# USB.net
KiCad netlist of a schematic drawn in Altium Designer
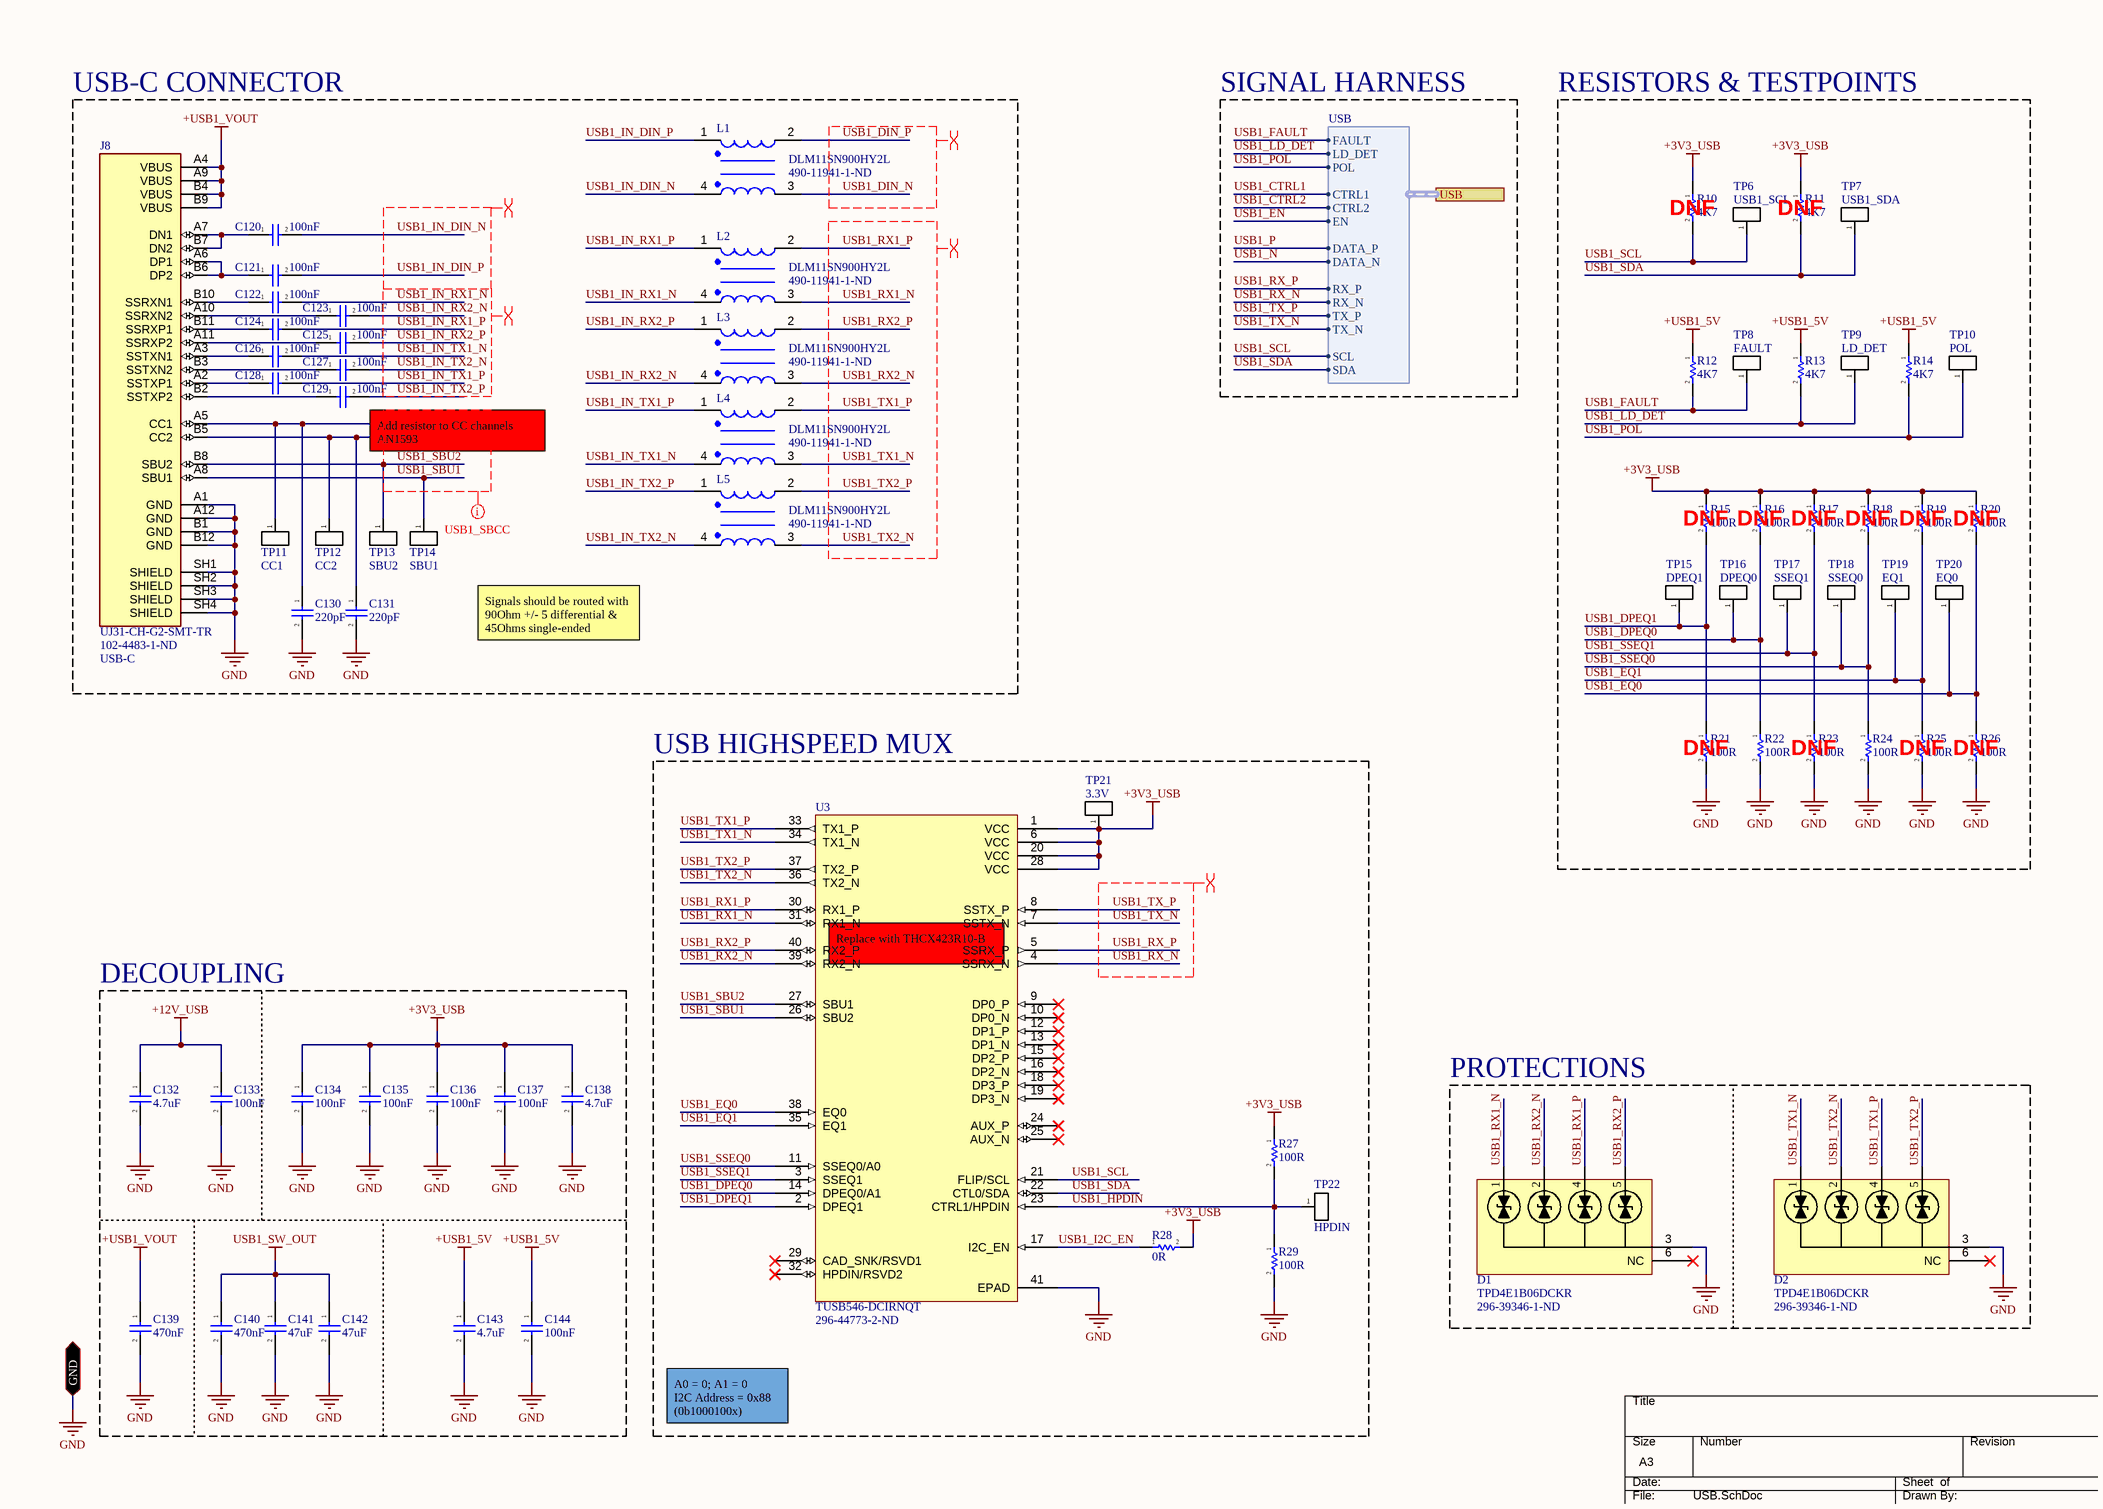
[diagram p0: USB.SchDoc]

(export (version "E")
  (design (tool "Eeschema 10.0.6"))
  (components
    (comp (ref "C120")
      (value "100nF")
      (footprint "CAP_0402")
      (description "Generic SMT Ceramic Capacitor")
      (libsource (lib "Symbols") (part "CAP_CER"))
    )
    (comp (ref "C121")
      (value "100nF")
      (footprint "CAP_0402")
      (description "Generic SMT Ceramic Capacitor")
      (libsource (lib "Symbols") (part "CAP_CER"))
    )
    (comp (ref "C122")
      (value "100nF")
      (footprint "CAP_0402")
      (description "Generic SMT Ceramic Capacitor")
      (libsource (lib "Symbols") (part "CAP_CER"))
    )
    (comp (ref "C123")
      (value "100nF")
      (footprint "CAP_0402")
      (description "Generic SMT Ceramic Capacitor")
      (libsource (lib "Symbols") (part "CAP_CER"))
    )
    (comp (ref "C124")
      (value "100nF")
      (footprint "CAP_0402")
      (description "Generic SMT Ceramic Capacitor")
      (libsource (lib "Symbols") (part "CAP_CER"))
    )
    (comp (ref "C125")
      (value "100nF")
      (footprint "CAP_0402")
      (description "Generic SMT Ceramic Capacitor")
      (libsource (lib "Symbols") (part "CAP_CER"))
    )
    (comp (ref "C126")
      (value "100nF")
      (footprint "CAP_0402")
      (description "Generic SMT Ceramic Capacitor")
      (libsource (lib "Symbols") (part "CAP_CER"))
    )
    (comp (ref "C127")
      (value "100nF")
      (footprint "CAP_0402")
      (description "Generic SMT Ceramic Capacitor")
      (libsource (lib "Symbols") (part "CAP_CER"))
    )
    (comp (ref "C128")
      (value "100nF")
      (footprint "CAP_0402")
      (description "Generic SMT Ceramic Capacitor")
      (libsource (lib "Symbols") (part "CAP_CER"))
    )
    (comp (ref "C129")
      (value "100nF")
      (footprint "CAP_0402")
      (description "Generic SMT Ceramic Capacitor")
      (libsource (lib "Symbols") (part "CAP_CER"))
    )
    (comp (ref "C130")
      (value "220pF")
      (footprint "CAP_0402")
      (description "Generic SMT Ceramic Capacitor")
      (libsource (lib "Symbols") (part "CAP_CER"))
    )
    (comp (ref "C131")
      (value "220pF")
      (footprint "CAP_0402")
      (description "Generic SMT Ceramic Capacitor")
      (libsource (lib "Symbols") (part "CAP_CER"))
    )
    (comp (ref "C132")
      (value "4.7uF")
      (footprint "CAP_0805")
      (description "Generic SMT Ceramic Capacitor")
      (libsource (lib "Symbols") (part "CAP_CER"))
    )
    (comp (ref "C133")
      (value "100nF")
      (footprint "CAP_0402")
      (description "Generic SMT Ceramic Capacitor")
      (libsource (lib "Symbols") (part "CAP_CER"))
    )
    (comp (ref "C134")
      (value "100nF")
      (footprint "CAP_0402")
      (description "Generic SMT Ceramic Capacitor")
      (libsource (lib "Symbols") (part "CAP_CER"))
    )
    (comp (ref "C135")
      (value "100nF")
      (footprint "CAP_0402")
      (description "Generic SMT Ceramic Capacitor")
      (libsource (lib "Symbols") (part "CAP_CER"))
    )
    (comp (ref "C136")
      (value "100nF")
      (footprint "CAP_0402")
      (description "Generic SMT Ceramic Capacitor")
      (libsource (lib "Symbols") (part "CAP_CER"))
    )
    (comp (ref "C137")
      (value "100nF")
      (footprint "CAP_0402")
      (description "Generic SMT Ceramic Capacitor")
      (libsource (lib "Symbols") (part "CAP_CER"))
    )
    (comp (ref "C138")
      (value "4.7uF")
      (footprint "CAP_0805")
      (description "Generic SMT Ceramic Capacitor")
      (libsource (lib "Symbols") (part "CAP_CER"))
    )
    (comp (ref "C139")
      (value "470nF")
      (footprint "CAP_0402")
      (description "Generic SMT Ceramic Capacitor")
      (libsource (lib "Symbols") (part "CAP_CER"))
    )
    (comp (ref "C140")
      (value "470nF")
      (footprint "CAP_0402")
      (description "Generic SMT Ceramic Capacitor")
      (libsource (lib "Symbols") (part "CAP_CER"))
    )
    (comp (ref "C141")
      (value "47uF")
      (footprint "CAP_1206")
      (description "Generic SMT Ceramic Capacitor")
      (libsource (lib "Symbols") (part "CAP_CER"))
    )
    (comp (ref "C142")
      (value "47uF")
      (footprint "CAP_1206")
      (description "Generic SMT Ceramic Capacitor")
      (libsource (lib "Symbols") (part "CAP_CER"))
    )
    (comp (ref "C143")
      (value "4.7uF")
      (footprint "CAP_0805")
      (description "Generic SMT Ceramic Capacitor")
      (libsource (lib "Symbols") (part "CAP_CER"))
    )
    (comp (ref "C144")
      (value "100nF")
      (footprint "CAP_0402")
      (description "Generic SMT Ceramic Capacitor")
      (libsource (lib "Symbols") (part "CAP_CER"))
    )
    (comp (ref "D1")
      (value "TPD4E1B06DCKR")
      (footprint "TPD4E1B06DCKR")
      (description "TVS DIODE 5.5VWM 14.5VC SC70-6")
      (fields
        (field (name "MFR") "Texas Instruments")
        (field (name "SUPPLIER PART NUMBER 1") "296-39346-1-ND")
      )
      (libsource (lib "CryptLib") (part "DIODE_TPD4E1B06DCKR"))
    )
    (comp (ref "D2")
      (value "TPD4E1B06DCKR")
      (footprint "TPD4E1B06DCKR")
      (description "TVS DIODE 5.5VWM 14.5VC SC70-6")
      (fields
        (field (name "MFR") "Texas Instruments")
        (field (name "SUPPLIER PART NUMBER 1") "296-39346-1-ND")
      )
      (libsource (lib "CryptLib") (part "DIODE_TPD4E1B06DCKR"))
    )
    (comp (ref "J8")
      (value "UJ31-CH-G2-SMT-TR")
      (footprint "UJ31-CH-G2-SMT-TR")
      (description "Type C, USB 3.1 Gen 2, 5 A, Right Angle, Surface Mount _SMT_, USB Receptacle")
      (fields
        (field (name "MFR") "CUI Devices")
        (field (name "DIGIKEY PART NUMBER") "102-4483-1-ND")
        (field (name "CONNECTOR TYPE") "USB-C")
        (field (name "SUPPLIER PART NUMBER 1") "102-4483-1-ND")
      )
      (libsource (lib "CryptLib") (part "CONN_UJ31-CH-G2-SMT-TR"))
    )
    (comp (ref "L1")
      (value "DLM11SN900HY2L")
      (footprint "DLM11SN900HY2L")
      (description "2 Line Common Mode Choke Surface Mount 90 Ohms @ 100MHz 100mA DCR 1.38Ohm")
      (fields (field (name "SUPPLIER PART NUMBER 1") "490-11941-1-ND"))
      (libsource (lib "CryptLib") (part "IND_DLM11SN900HY2L"))
    )
    (comp (ref "L2")
      (value "DLM11SN900HY2L")
      (footprint "DLM11SN900HY2L")
      (description "2 Line Common Mode Choke Surface Mount 90 Ohms @ 100MHz 100mA DCR 1.38Ohm")
      (fields (field (name "SUPPLIER PART NUMBER 1") "490-11941-1-ND"))
      (libsource (lib "CryptLib") (part "IND_DLM11SN900HY2L"))
    )
    (comp (ref "L3")
      (value "DLM11SN900HY2L")
      (footprint "DLM11SN900HY2L")
      (description "2 Line Common Mode Choke Surface Mount 90 Ohms @ 100MHz 100mA DCR 1.38Ohm")
      (fields (field (name "SUPPLIER PART NUMBER 1") "490-11941-1-ND"))
      (libsource (lib "CryptLib") (part "IND_DLM11SN900HY2L"))
    )
    (comp (ref "L4")
      (value "DLM11SN900HY2L")
      (footprint "DLM11SN900HY2L")
      (description "2 Line Common Mode Choke Surface Mount 90 Ohms @ 100MHz 100mA DCR 1.38Ohm")
      (fields (field (name "SUPPLIER PART NUMBER 1") "490-11941-1-ND"))
      (libsource (lib "CryptLib") (part "IND_DLM11SN900HY2L"))
    )
    (comp (ref "L5")
      (value "DLM11SN900HY2L")
      (footprint "DLM11SN900HY2L")
      (description "2 Line Common Mode Choke Surface Mount 90 Ohms @ 100MHz 100mA DCR 1.38Ohm")
      (fields (field (name "SUPPLIER PART NUMBER 1") "490-11941-1-ND"))
      (libsource (lib "CryptLib") (part "IND_DLM11SN900HY2L"))
    )
    (comp (ref "R10")
      (value "4K7")
      (footprint "RES_0603")
      (description "Resistor")
      (fields (field (name "POWER") "1/16W") (field (name "TOLERANCE") "10%"))
      (libsource (lib "Symbols") (part "RESISTOR"))
    )
    (comp (ref "R11")
      (value "4K7")
      (footprint "RES_0603")
      (description "Resistor")
      (fields (field (name "POWER") "1/16W") (field (name "TOLERANCE") "10%"))
      (libsource (lib "Symbols") (part "RESISTOR"))
    )
    (comp (ref "R12")
      (value "4K7")
      (footprint "RES_0603")
      (description "Resistor")
      (fields (field (name "POWER") "1/16W") (field (name "TOLERANCE") "10%"))
      (libsource (lib "Symbols") (part "RESISTOR"))
    )
    (comp (ref "R13")
      (value "4K7")
      (footprint "RES_0603")
      (description "Resistor")
      (fields (field (name "POWER") "1/16W") (field (name "TOLERANCE") "10%"))
      (libsource (lib "Symbols") (part "RESISTOR"))
    )
    (comp (ref "R14")
      (value "4K7")
      (footprint "RES_0603")
      (description "Resistor")
      (fields (field (name "POWER") "1/16W") (field (name "TOLERANCE") "10%"))
      (libsource (lib "Symbols") (part "RESISTOR"))
    )
    (comp (ref "R15")
      (value "100R")
      (footprint "RES_0402")
      (description "Resistor")
      (fields (field (name "POWER") "1/8W") (field (name "TOLERANCE") "10%"))
      (libsource (lib "Symbols") (part "RESISTOR"))
    )
    (comp (ref "R16")
      (value "100R")
      (footprint "RES_0402")
      (description "Resistor")
      (fields (field (name "POWER") "1/8W") (field (name "TOLERANCE") "10%"))
      (libsource (lib "Symbols") (part "RESISTOR"))
    )
    (comp (ref "R17")
      (value "100R")
      (footprint "RES_0402")
      (description "Resistor")
      (fields (field (name "POWER") "1/8W") (field (name "TOLERANCE") "10%"))
      (libsource (lib "Symbols") (part "RESISTOR"))
    )
    (comp (ref "R18")
      (value "100R")
      (footprint "RES_0402")
      (description "Resistor")
      (fields (field (name "POWER") "1/8W") (field (name "TOLERANCE") "10%"))
      (libsource (lib "Symbols") (part "RESISTOR"))
    )
    (comp (ref "R19")
      (value "100R")
      (footprint "RES_0402")
      (description "Resistor")
      (fields (field (name "POWER") "1/8W") (field (name "TOLERANCE") "10%"))
      (libsource (lib "Symbols") (part "RESISTOR"))
    )
    (comp (ref "R20")
      (value "100R")
      (footprint "RES_0402")
      (description "Resistor")
      (fields (field (name "POWER") "1/8W") (field (name "TOLERANCE") "10%"))
      (libsource (lib "Symbols") (part "RESISTOR"))
    )
    (comp (ref "R21")
      (value "100R")
      (footprint "RES_0402")
      (description "Resistor")
      (fields (field (name "POWER") "1/8W") (field (name "TOLERANCE") "10%"))
      (libsource (lib "Symbols") (part "RESISTOR"))
    )
    (comp (ref "R22")
      (value "100R")
      (footprint "RES_0402")
      (description "Resistor")
      (fields (field (name "POWER") "1/8W") (field (name "TOLERANCE") "10%"))
      (libsource (lib "Symbols") (part "RESISTOR"))
    )
    (comp (ref "R23")
      (value "100R")
      (footprint "RES_0402")
      (description "Resistor")
      (fields (field (name "POWER") "1/8W") (field (name "TOLERANCE") "10%"))
      (libsource (lib "Symbols") (part "RESISTOR"))
    )
    (comp (ref "R24")
      (value "100R")
      (footprint "RES_0402")
      (description "Resistor")
      (fields (field (name "POWER") "1/8W") (field (name "TOLERANCE") "10%"))
      (libsource (lib "Symbols") (part "RESISTOR"))
    )
    (comp (ref "R25")
      (value "100R")
      (footprint "RES_0402")
      (description "Resistor")
      (fields (field (name "POWER") "1/8W") (field (name "TOLERANCE") "10%"))
      (libsource (lib "Symbols") (part "RESISTOR"))
    )
    (comp (ref "R26")
      (value "100R")
      (footprint "RES_0402")
      (description "Resistor")
      (fields (field (name "POWER") "1/8W") (field (name "TOLERANCE") "10%"))
      (libsource (lib "Symbols") (part "RESISTOR"))
    )
    (comp (ref "R27")
      (value "100R")
      (footprint "RES_0402")
      (description "Resistor")
      (fields (field (name "POWER") "1/8W") (field (name "TOLERANCE") "10%"))
      (libsource (lib "Symbols") (part "RESISTOR"))
    )
    (comp (ref "R28")
      (value "0R")
      (footprint "RES_0603")
      (description "Resistor")
      (fields (field (name "POWER") "1/8W") (field (name "TOLERANCE") "10%"))
      (libsource (lib "Symbols") (part "RESISTOR"))
    )
    (comp (ref "R29")
      (value "100R")
      (footprint "RES_0402")
      (description "Resistor")
      (fields (field (name "POWER") "1/8W") (field (name "TOLERANCE") "10%"))
      (libsource (lib "Symbols") (part "RESISTOR"))
    )
    (comp (ref "TP6")
      (value "USB1_SCL")
      (footprint "TP_PAD_SMALL")
      (description "Test Point")
      (libsource (lib "Symbols") (part "TESTPOINT"))
    )
    (comp (ref "TP7")
      (value "USB1_SDA")
      (footprint "TP_PAD_SMALL")
      (description "Test Point")
      (libsource (lib "Symbols") (part "TESTPOINT"))
    )
    (comp (ref "TP8")
      (value "FAULT")
      (footprint "TP_PAD_TINY")
      (description "Test Point")
      (libsource (lib "Symbols") (part "TESTPOINT"))
    )
    (comp (ref "TP9")
      (value "LD_DET")
      (footprint "TP_PAD_TINY")
      (description "Test Point")
      (libsource (lib "Symbols") (part "TESTPOINT"))
    )
    (comp (ref "TP10")
      (value "POL")
      (footprint "TP_PAD_TINY")
      (description "Test Point")
      (libsource (lib "Symbols") (part "TESTPOINT"))
    )
    (comp (ref "TP11")
      (value "CC1")
      (footprint "TP_PAD_TINY")
      (description "Test Point")
      (libsource (lib "Symbols") (part "TESTPOINT"))
    )
    (comp (ref "TP12")
      (value "CC2")
      (footprint "TP_PAD_TINY")
      (description "Test Point")
      (libsource (lib "Symbols") (part "TESTPOINT"))
    )
    (comp (ref "TP13")
      (value "SBU2")
      (footprint "TP_PAD_TINY")
      (description "Test Point")
      (libsource (lib "Symbols") (part "TESTPOINT"))
    )
    (comp (ref "TP14")
      (value "SBU1")
      (footprint "TP_PAD_TINY")
      (description "Test Point")
      (libsource (lib "Symbols") (part "TESTPOINT"))
    )
    (comp (ref "TP15")
      (value "DPEQ1")
      (footprint "TP_PAD_TINY")
      (description "Test Point")
      (libsource (lib "Symbols") (part "TESTPOINT"))
    )
    (comp (ref "TP16")
      (value "DPEQ0")
      (footprint "TP_PAD_TINY")
      (description "Test Point")
      (libsource (lib "Symbols") (part "TESTPOINT"))
    )
    (comp (ref "TP17")
      (value "SSEQ1")
      (footprint "TP_PAD_TINY")
      (description "Test Point")
      (libsource (lib "Symbols") (part "TESTPOINT"))
    )
    (comp (ref "TP18")
      (value "SSEQ0")
      (footprint "TP_PAD_TINY")
      (description "Test Point")
      (libsource (lib "Symbols") (part "TESTPOINT"))
    )
    (comp (ref "TP19")
      (value "EQ1")
      (footprint "TP_PAD_TINY")
      (description "Test Point")
      (libsource (lib "Symbols") (part "TESTPOINT"))
    )
    (comp (ref "TP20")
      (value "EQ0")
      (footprint "TP_PAD_TINY")
      (description "Test Point")
      (libsource (lib "Symbols") (part "TESTPOINT"))
    )
    (comp (ref "TP21")
      (value "3.3V")
      (footprint "TP_PAD")
      (description "Test Point")
      (libsource (lib "Symbols") (part "TESTPOINT"))
    )
    (comp (ref "TP22")
      (value "HPDIN")
      (footprint "TP_PAD_TINY")
      (description "Test Point")
      (libsource (lib "Symbols") (part "TESTPOINT"))
    )
    (comp (ref "U3")
      (value "TUSB546-DCIRNQT")
      (footprint "TUSB546-DCIRNQT")
      (description "Buffer, ReDriver 2 Channel 8.1Gbps 40-WQFN (4x6)")
      (fields
        (field (name "MFR") "Texas Instruments")
        (field (name "SUPPLIER PART NUMBER 1") "296-44773-2-ND")
      )
      (libsource (lib "CryptLib") (part "IC_TUSB546-DCIRNQT"))
    )
  )
  (nets
    (net (code "2") (name "+3V3_USB") (class "Default")
      (node (ref "C134") (pin "1") (pinfunction "1_1") (pintype "passive"))
      (node (ref "C135") (pin "1") (pinfunction "1_1") (pintype "passive"))
      (node (ref "C136") (pin "1") (pinfunction "1_1") (pintype "passive"))
      (node (ref "C137") (pin "1") (pinfunction "1_1") (pintype "passive"))
      (node (ref "C138") (pin "1") (pinfunction "1_1") (pintype "passive"))
      (node (ref "R10") (pin "1") (pinfunction "1_1") (pintype "passive"))
      (node (ref "R11") (pin "1") (pinfunction "1_1") (pintype "passive"))
      (node (ref "R15") (pin "1") (pinfunction "1_1") (pintype "passive"))
      (node (ref "R16") (pin "1") (pinfunction "1_1") (pintype "passive"))
      (node (ref "R17") (pin "1") (pinfunction "1_1") (pintype "passive"))
      (node (ref "R18") (pin "1") (pinfunction "1_1") (pintype "passive"))
      (node (ref "R19") (pin "1") (pinfunction "1_1") (pintype "passive"))
      (node (ref "R20") (pin "1") (pinfunction "1_1") (pintype "passive"))
      (node (ref "R27") (pin "1") (pinfunction "1_1") (pintype "passive"))
      (node (ref "R28") (pin "2") (pinfunction "2_2") (pintype "passive"))
      (node (ref "TP21") (pin "1") (pinfunction "A_1") (pintype "passive"))
      (node (ref "U3") (pin "1") (pinfunction "VCC_1") (pintype "power_in"))
      (node (ref "U3") (pin "20") (pinfunction "VCC_20") (pintype "power_in"))
      (node (ref "U3") (pin "28") (pinfunction "VCC_28") (pintype "power_in"))
      (node (ref "U3") (pin "6") (pinfunction "VCC_6") (pintype "power_in"))
    )
    (net (code "3") (name "+12V_USB") (class "Default")
      (node (ref "C132") (pin "1") (pinfunction "1_1") (pintype "passive"))
      (node (ref "C133") (pin "1") (pinfunction "1_1") (pintype "passive"))
    )
    (net (code "4") (name "+USB1_5V") (class "Default")
      (node (ref "C143") (pin "1") (pinfunction "1_1") (pintype "passive"))
      (node (ref "C144") (pin "1") (pinfunction "1_1") (pintype "passive"))
      (node (ref "R12") (pin "1") (pinfunction "1_1") (pintype "passive"))
      (node (ref "R13") (pin "1") (pinfunction "1_1") (pintype "passive"))
      (node (ref "R14") (pin "1") (pinfunction "1_1") (pintype "passive"))
    )
    (net (code "5") (name "+USB1_VOUT") (class "Default")
      (node (ref "C139") (pin "1") (pinfunction "1_1") (pintype "passive"))
      (node (ref "J8") (pin "A4") (pinfunction "VBUS_A4") (pintype "power_in"))
      (node (ref "J8") (pin "A9") (pinfunction "VBUS_A9") (pintype "power_in"))
      (node (ref "J8") (pin "B4") (pinfunction "VBUS_B4") (pintype "power_in"))
      (node (ref "J8") (pin "B9") (pinfunction "VBUS_B9") (pintype "power_in"))
    )
    (net (code "6") (name "/USB1_CC1") (class "Default")
      (node (ref "C130") (pin "1") (pinfunction "1_1") (pintype "passive"))
      (node (ref "J8") (pin "A5") (pinfunction "CC1_A5") (pintype "bidirectional"))
      (node (ref "TP11") (pin "1") (pinfunction "A_1") (pintype "passive"))
    )
    (net (code "7") (name "/USB1_CC2") (class "Default")
      (node (ref "C131") (pin "1") (pinfunction "1_1") (pintype "passive"))
      (node (ref "J8") (pin "B5") (pinfunction "CC2_B5") (pintype "bidirectional"))
      (node (ref "TP12") (pin "1") (pinfunction "A_1") (pintype "passive"))
    )
    (net (code "10") (name "/USB1_DIN_N") (class "Default")
      (node (ref "L1") (pin "3") (pinfunction "3_3") (pintype "passive"))
    )
    (net (code "11") (name "/USB1_DIN_P") (class "Default")
      (node (ref "L1") (pin "2") (pinfunction "2_2") (pintype "passive"))
    )
    (net (code "12") (name "/USB1_DPEQ0") (class "Default")
      (node (ref "R16") (pin "2") (pinfunction "2_2") (pintype "passive"))
      (node (ref "R22") (pin "1") (pinfunction "1_1") (pintype "passive"))
      (node (ref "TP16") (pin "1") (pinfunction "A_1") (pintype "passive"))
      (node (ref "U3") (pin "14") (pinfunction "DPEQ0/A1_14") (pintype "input"))
    )
    (net (code "13") (name "/USB1_DPEQ1") (class "Default")
      (node (ref "R15") (pin "2") (pinfunction "2_2") (pintype "passive"))
      (node (ref "R21") (pin "1") (pinfunction "1_1") (pintype "passive"))
      (node (ref "TP15") (pin "1") (pinfunction "A_1") (pintype "passive"))
      (node (ref "U3") (pin "2") (pinfunction "DPEQ1_2") (pintype "input"))
    )
    (net (code "15") (name "/USB1_EQ0") (class "Default")
      (node (ref "R20") (pin "2") (pinfunction "2_2") (pintype "passive"))
      (node (ref "R26") (pin "1") (pinfunction "1_1") (pintype "passive"))
      (node (ref "TP20") (pin "1") (pinfunction "A_1") (pintype "passive"))
      (node (ref "U3") (pin "38") (pinfunction "EQ0_38") (pintype "input"))
    )
    (net (code "16") (name "/USB1_EQ1") (class "Default")
      (node (ref "R19") (pin "2") (pinfunction "2_2") (pintype "passive"))
      (node (ref "R25") (pin "1") (pinfunction "1_1") (pintype "passive"))
      (node (ref "TP19") (pin "1") (pinfunction "A_1") (pintype "passive"))
      (node (ref "U3") (pin "35") (pinfunction "EQ1_35") (pintype "input"))
    )
    (net (code "17") (name "/USB1_FAULT") (class "Default")
      (node (ref "R12") (pin "2") (pinfunction "2_2") (pintype "passive"))
      (node (ref "TP8") (pin "1") (pinfunction "A_1") (pintype "passive"))
    )
    (net (code "18") (name "/USB1_HPDIN") (class "Default")
      (node (ref "R27") (pin "2") (pinfunction "2_2") (pintype "passive"))
      (node (ref "R29") (pin "1") (pinfunction "1_1") (pintype "passive"))
      (node (ref "TP22") (pin "1") (pinfunction "A_1") (pintype "passive"))
      (node (ref "U3") (pin "23") (pinfunction "CTRL1/HPDIN_23") (pintype "input"))
    )
    (net (code "19") (name "/USB1_I2C_EN") (class "Default")
      (node (ref "R28") (pin "1") (pinfunction "1_1") (pintype "passive"))
      (node (ref "U3") (pin "17") (pinfunction "I2C_EN_17") (pintype "input"))
    )
    (net (code "20") (name "/USB1_IN_DIN_N") (class "Default")
      (node (ref "C120") (pin "2") (pinfunction "2_2") (pintype "passive"))
      (node (ref "L1") (pin "4") (pinfunction "4_4") (pintype "passive"))
    )
    (net (code "21") (name "/USB1_IN_DIN_P") (class "Default")
      (node (ref "C121") (pin "2") (pinfunction "2_2") (pintype "passive"))
      (node (ref "L1") (pin "1") (pinfunction "1_1") (pintype "passive"))
    )
    (net (code "22") (name "/USB1_IN_RX1_N") (class "Default")
      (node (ref "C122") (pin "2") (pinfunction "2_2") (pintype "passive"))
      (node (ref "L2") (pin "4") (pinfunction "4_4") (pintype "passive"))
    )
    (net (code "23") (name "/USB1_IN_RX1_P") (class "Default")
      (node (ref "C124") (pin "2") (pinfunction "2_2") (pintype "passive"))
      (node (ref "L2") (pin "1") (pinfunction "1_1") (pintype "passive"))
    )
    (net (code "24") (name "/USB1_IN_RX2_N") (class "Default")
      (node (ref "C123") (pin "2") (pinfunction "2_2") (pintype "passive"))
      (node (ref "L3") (pin "4") (pinfunction "4_4") (pintype "passive"))
    )
    (net (code "25") (name "/USB1_IN_RX2_P") (class "Default")
      (node (ref "C125") (pin "2") (pinfunction "2_2") (pintype "passive"))
      (node (ref "L3") (pin "1") (pinfunction "1_1") (pintype "passive"))
    )
    (net (code "26") (name "/USB1_IN_TX1_N") (class "Default")
      (node (ref "C126") (pin "2") (pinfunction "2_2") (pintype "passive"))
      (node (ref "L4") (pin "4") (pinfunction "4_4") (pintype "passive"))
    )
    (net (code "27") (name "/USB1_IN_TX1_P") (class "Default")
      (node (ref "C128") (pin "2") (pinfunction "2_2") (pintype "passive"))
      (node (ref "L4") (pin "1") (pinfunction "1_1") (pintype "passive"))
    )
    (net (code "28") (name "/USB1_IN_TX2_N") (class "Default")
      (node (ref "C127") (pin "2") (pinfunction "2_2") (pintype "passive"))
      (node (ref "L5") (pin "4") (pinfunction "4_4") (pintype "passive"))
    )
    (net (code "29") (name "/USB1_IN_TX2_P") (class "Default")
      (node (ref "C129") (pin "2") (pinfunction "2_2") (pintype "passive"))
      (node (ref "L5") (pin "1") (pinfunction "1_1") (pintype "passive"))
    )
    (net (code "30") (name "/USB1_LD_DET") (class "Default")
      (node (ref "R13") (pin "2") (pinfunction "2_2") (pintype "passive"))
      (node (ref "TP9") (pin "1") (pinfunction "A_1") (pintype "passive"))
    )
    (net (code "33") (name "/USB1_POL") (class "Default")
      (node (ref "R14") (pin "2") (pinfunction "2_2") (pintype "passive"))
      (node (ref "TP10") (pin "1") (pinfunction "A_1") (pintype "passive"))
    )
    (net (code "34") (name "/USB1_RX1_N") (class "Default")
      (node (ref "D1") (pin "1") (pinfunction "A_1") (pintype "passive"))
      (node (ref "L2") (pin "3") (pinfunction "3_3") (pintype "passive"))
      (node (ref "U3") (pin "31") (pinfunction "RX1_N_31") (pintype "bidirectional"))
    )
    (net (code "35") (name "/USB1_RX1_P") (class "Default")
      (node (ref "D1") (pin "4") (pinfunction "A_4") (pintype "passive"))
      (node (ref "L2") (pin "2") (pinfunction "2_2") (pintype "passive"))
      (node (ref "U3") (pin "30") (pinfunction "RX1_P_30") (pintype "bidirectional"))
    )
    (net (code "36") (name "/USB1_RX2_N") (class "Default")
      (node (ref "D1") (pin "2") (pinfunction "A_2") (pintype "passive"))
      (node (ref "L3") (pin "3") (pinfunction "3_3") (pintype "passive"))
      (node (ref "U3") (pin "39") (pinfunction "RX2_N_39") (pintype "bidirectional"))
    )
    (net (code "37") (name "/USB1_RX2_P") (class "Default")
      (node (ref "D1") (pin "5") (pinfunction "A_5") (pintype "passive"))
      (node (ref "L3") (pin "2") (pinfunction "2_2") (pintype "passive"))
      (node (ref "U3") (pin "40") (pinfunction "RX2_P_40") (pintype "bidirectional"))
    )
    (net (code "38") (name "/USB1_RX_N") (class "Default")
      (node (ref "U3") (pin "4") (pinfunction "SSRX_N_4") (pintype "output"))
    )
    (net (code "39") (name "/USB1_RX_P") (class "Default")
      (node (ref "U3") (pin "5") (pinfunction "SSRX_P_5") (pintype "output"))
    )
    (net (code "40") (name "/USB1_SBU1") (class "Default")
      (node (ref "J8") (pin "A8") (pinfunction "SBU1_A8") (pintype "bidirectional"))
      (node (ref "TP14") (pin "1") (pinfunction "A_1") (pintype "passive"))
      (node (ref "U3") (pin "26") (pinfunction "SBU2_26") (pintype "bidirectional"))
    )
    (net (code "41") (name "/USB1_SBU2") (class "Default")
      (node (ref "J8") (pin "B8") (pinfunction "SBU2_B8") (pintype "bidirectional"))
      (node (ref "TP13") (pin "1") (pinfunction "A_1") (pintype "passive"))
      (node (ref "U3") (pin "27") (pinfunction "SBU1_27") (pintype "bidirectional"))
    )
    (net (code "42") (name "/USB1_SCL") (class "Default")
      (node (ref "R10") (pin "2") (pinfunction "2_2") (pintype "passive"))
      (node (ref "TP6") (pin "1") (pinfunction "A_1") (pintype "passive"))
      (node (ref "U3") (pin "21") (pinfunction "FLIP/SCL_21") (pintype "input"))
    )
    (net (code "43") (name "/USB1_SDA") (class "Default")
      (node (ref "R11") (pin "2") (pinfunction "2_2") (pintype "passive"))
      (node (ref "TP7") (pin "1") (pinfunction "A_1") (pintype "passive"))
      (node (ref "U3") (pin "22") (pinfunction "CTL0/SDA_22") (pintype "bidirectional"))
    )
    (net (code "44") (name "/USB1_SSEQ0") (class "Default")
      (node (ref "R18") (pin "2") (pinfunction "2_2") (pintype "passive"))
      (node (ref "R24") (pin "1") (pinfunction "1_1") (pintype "passive"))
      (node (ref "TP18") (pin "1") (pinfunction "A_1") (pintype "passive"))
      (node (ref "U3") (pin "11") (pinfunction "SSEQ0/A0_11") (pintype "input"))
    )
    (net (code "45") (name "/USB1_SSEQ1") (class "Default")
      (node (ref "R17") (pin "2") (pinfunction "2_2") (pintype "passive"))
      (node (ref "R23") (pin "1") (pinfunction "1_1") (pintype "passive"))
      (node (ref "TP17") (pin "1") (pinfunction "A_1") (pintype "passive"))
      (node (ref "U3") (pin "3") (pinfunction "SSEQ1_3") (pintype "input"))
    )
    (net (code "46") (name "/USB1_TX1_N") (class "Default")
      (node (ref "D2") (pin "1") (pinfunction "A_1") (pintype "passive"))
      (node (ref "L4") (pin "3") (pinfunction "3_3") (pintype "passive"))
      (node (ref "U3") (pin "34") (pinfunction "TX1_N_34") (pintype "output"))
    )
    (net (code "47") (name "/USB1_TX1_P") (class "Default")
      (node (ref "D2") (pin "4") (pinfunction "A_4") (pintype "passive"))
      (node (ref "L4") (pin "2") (pinfunction "2_2") (pintype "passive"))
      (node (ref "U3") (pin "33") (pinfunction "TX1_P_33") (pintype "output"))
    )
    (net (code "48") (name "/USB1_TX2_N") (class "Default")
      (node (ref "D2") (pin "2") (pinfunction "A_2") (pintype "passive"))
      (node (ref "L5") (pin "3") (pinfunction "3_3") (pintype "passive"))
      (node (ref "U3") (pin "36") (pinfunction "TX2_N_36") (pintype "output"))
    )
    (net (code "49") (name "/USB1_TX2_P") (class "Default")
      (node (ref "D2") (pin "5") (pinfunction "A_5") (pintype "passive"))
      (node (ref "L5") (pin "2") (pinfunction "2_2") (pintype "passive"))
      (node (ref "U3") (pin "37") (pinfunction "TX2_P_37") (pintype "output"))
    )
    (net (code "50") (name "/USB1_TX_N") (class "Default")
      (node (ref "U3") (pin "7") (pinfunction "SSTX_N_7") (pintype "input"))
    )
    (net (code "51") (name "/USB1_TX_P") (class "Default")
      (node (ref "U3") (pin "8") (pinfunction "SSTX_P_8") (pintype "input"))
    )
    (net (code "53") (name "GND") (class "Default")
      (node (ref "C130") (pin "2") (pinfunction "2_2") (pintype "passive"))
      (node (ref "C131") (pin "2") (pinfunction "2_2") (pintype "passive"))
      (node (ref "C132") (pin "2") (pinfunction "2_2") (pintype "passive"))
      (node (ref "C133") (pin "2") (pinfunction "2_2") (pintype "passive"))
      (node (ref "C134") (pin "2") (pinfunction "2_2") (pintype "passive"))
      (node (ref "C135") (pin "2") (pinfunction "2_2") (pintype "passive"))
      (node (ref "C136") (pin "2") (pinfunction "2_2") (pintype "passive"))
      (node (ref "C137") (pin "2") (pinfunction "2_2") (pintype "passive"))
      (node (ref "C138") (pin "2") (pinfunction "2_2") (pintype "passive"))
      (node (ref "C139") (pin "2") (pinfunction "2_2") (pintype "passive"))
      (node (ref "C140") (pin "2") (pinfunction "2_2") (pintype "passive"))
      (node (ref "C141") (pin "2") (pinfunction "2_2") (pintype "passive"))
      (node (ref "C142") (pin "2") (pinfunction "2_2") (pintype "passive"))
      (node (ref "C143") (pin "2") (pinfunction "2_2") (pintype "passive"))
      (node (ref "C144") (pin "2") (pinfunction "2_2") (pintype "passive"))
      (node (ref "D1") (pin "3") (pinfunction "GND_3") (pintype "passive"))
      (node (ref "D2") (pin "3") (pinfunction "GND_3") (pintype "passive"))
      (node (ref "J8") (pin "A1") (pinfunction "GND_A1") (pintype "power_in"))
      (node (ref "J8") (pin "A12") (pinfunction "GND_A12") (pintype "power_in"))
      (node (ref "J8") (pin "B1") (pinfunction "GND_B1") (pintype "power_in"))
      (node (ref "J8") (pin "B12") (pinfunction "GND_B12") (pintype "power_in"))
      (node (ref "J8") (pin "SH1") (pinfunction "SHIELD_SH1") (pintype "power_in"))
      (node (ref "J8") (pin "SH2") (pinfunction "SHIELD_SH2") (pintype "power_in"))
      (node (ref "J8") (pin "SH3") (pinfunction "SHIELD_SH3") (pintype "power_in"))
      (node (ref "J8") (pin "SH4") (pinfunction "SHIELD_SH4") (pintype "power_in"))
      (node (ref "R21") (pin "2") (pinfunction "2_2") (pintype "passive"))
      (node (ref "R22") (pin "2") (pinfunction "2_2") (pintype "passive"))
      (node (ref "R23") (pin "2") (pinfunction "2_2") (pintype "passive"))
      (node (ref "R24") (pin "2") (pinfunction "2_2") (pintype "passive"))
      (node (ref "R25") (pin "2") (pinfunction "2_2") (pintype "passive"))
      (node (ref "R26") (pin "2") (pinfunction "2_2") (pintype "passive"))
      (node (ref "R29") (pin "2") (pinfunction "2_2") (pintype "passive"))
      (node (ref "U3") (pin "41") (pinfunction "EPAD_41") (pintype "power_in"))
    )
    (net (code "54") (name "Net-(J8-DN1)") (class "Default")
      (node (ref "C120") (pin "1") (pinfunction "1_1") (pintype "passive"))
      (node (ref "J8") (pin "A7") (pinfunction "DN1_A7") (pintype "bidirectional"))
      (node (ref "J8") (pin "B7") (pinfunction "DN2_B7") (pintype "bidirectional"))
    )
    (net (code "55") (name "Net-(J8-DP1)") (class "Default")
      (node (ref "C121") (pin "1") (pinfunction "1_1") (pintype "passive"))
      (node (ref "J8") (pin "A6") (pinfunction "DP1_A6") (pintype "bidirectional"))
      (node (ref "J8") (pin "B6") (pinfunction "DP2_B6") (pintype "bidirectional"))
    )
    (net (code "56") (name "Net-(J8-SSRXN1)") (class "Default")
      (node (ref "C122") (pin "1") (pinfunction "1_1") (pintype "passive"))
      (node (ref "J8") (pin "B10") (pinfunction "SSRXN1_B10") (pintype "bidirectional"))
    )
    (net (code "57") (name "Net-(J8-SSRXN2)") (class "Default")
      (node (ref "C123") (pin "1") (pinfunction "1_1") (pintype "passive"))
      (node (ref "J8") (pin "A10") (pinfunction "SSRXN2_A10") (pintype "bidirectional"))
    )
    (net (code "58") (name "Net-(J8-SSRXP1)") (class "Default")
      (node (ref "C124") (pin "1") (pinfunction "1_1") (pintype "passive"))
      (node (ref "J8") (pin "B11") (pinfunction "SSRXP1_B11") (pintype "bidirectional"))
    )
    (net (code "59") (name "Net-(J8-SSRXP2)") (class "Default")
      (node (ref "C125") (pin "1") (pinfunction "1_1") (pintype "passive"))
      (node (ref "J8") (pin "A11") (pinfunction "SSRXP2_A11") (pintype "bidirectional"))
    )
    (net (code "60") (name "Net-(J8-SSTXN1)") (class "Default")
      (node (ref "C126") (pin "1") (pinfunction "1_1") (pintype "passive"))
      (node (ref "J8") (pin "A3") (pinfunction "SSTXN1_A3") (pintype "bidirectional"))
    )
    (net (code "61") (name "Net-(J8-SSTXN2)") (class "Default")
      (node (ref "C127") (pin "1") (pinfunction "1_1") (pintype "passive"))
      (node (ref "J8") (pin "B3") (pinfunction "SSTXN2_B3") (pintype "bidirectional"))
    )
    (net (code "62") (name "Net-(J8-SSTXP1)") (class "Default")
      (node (ref "C128") (pin "1") (pinfunction "1_1") (pintype "passive"))
      (node (ref "J8") (pin "A2") (pinfunction "SSTXP1_A2") (pintype "bidirectional"))
    )
    (net (code "63") (name "Net-(J8-SSTXP2)") (class "Default")
      (node (ref "C129") (pin "1") (pinfunction "1_1") (pintype "passive"))
      (node (ref "J8") (pin "B2") (pinfunction "SSTXP2_B2") (pintype "bidirectional"))
    )
    (net (code "64") (name "USB1_SW_OUT") (class "Default")
      (node (ref "C140") (pin "1") (pinfunction "1_1") (pintype "passive"))
      (node (ref "C141") (pin "1") (pinfunction "1_1") (pintype "passive"))
      (node (ref "C142") (pin "1") (pinfunction "1_1") (pintype "passive"))
    )
    (net (code "65") (name "unconnected-(D1-NC-Pad6)") (class "Default")
      (node (ref "D1") (pin "6") (pinfunction "NC_6") (pintype "passive+no_connect"))
    )
    (net (code "66") (name "unconnected-(D2-NC-Pad6)") (class "Default")
      (node (ref "D2") (pin "6") (pinfunction "NC_6") (pintype "passive+no_connect"))
    )
    (net (code "67") (name "unconnected-(U3-AUX_N-Pad25)") (class "Default")
      (node (ref "U3") (pin "25") (pinfunction "AUX_N_25") (pintype "bidirectional+no_connect"))
    )
    (net (code "68") (name "unconnected-(U3-AUX_P-Pad24)") (class "Default")
      (node (ref "U3") (pin "24") (pinfunction "AUX_P_24") (pintype "bidirectional+no_connect"))
    )
    (net (code "69") (name "unconnected-(U3-CAD_SNK{slash}RSVD1-Pad29)") (class "Default")
      (node (ref "U3") (pin "29") (pinfunction "CAD_SNK/RSVD1_29") (pintype "bidirectional+no_connect"))
    )
    (net (code "70") (name "unconnected-(U3-DP0_N-Pad10)") (class "Default")
      (node (ref "U3") (pin "10") (pinfunction "DP0_N_10") (pintype "input+no_connect"))
    )
    (net (code "71") (name "unconnected-(U3-DP0_P-Pad9)") (class "Default")
      (node (ref "U3") (pin "9") (pinfunction "DP0_P_9") (pintype "input+no_connect"))
    )
    (net (code "72") (name "unconnected-(U3-DP1_N-Pad13)") (class "Default")
      (node (ref "U3") (pin "13") (pinfunction "DP1_N_13") (pintype "input+no_connect"))
    )
    (net (code "73") (name "unconnected-(U3-DP1_P-Pad12)") (class "Default")
      (node (ref "U3") (pin "12") (pinfunction "DP1_P_12") (pintype "input+no_connect"))
    )
    (net (code "74") (name "unconnected-(U3-DP2_N-Pad16)") (class "Default")
      (node (ref "U3") (pin "16") (pinfunction "DP2_N_16") (pintype "input+no_connect"))
    )
    (net (code "75") (name "unconnected-(U3-DP2_P-Pad15)") (class "Default")
      (node (ref "U3") (pin "15") (pinfunction "DP2_P_15") (pintype "input+no_connect"))
    )
    (net (code "76") (name "unconnected-(U3-DP3_N-Pad19)") (class "Default")
      (node (ref "U3") (pin "19") (pinfunction "DP3_N_19") (pintype "input+no_connect"))
    )
    (net (code "77") (name "unconnected-(U3-DP3_P-Pad18)") (class "Default")
      (node (ref "U3") (pin "18") (pinfunction "DP3_P_18") (pintype "input+no_connect"))
    )
    (net (code "78") (name "unconnected-(U3-HPDIN{slash}RSVD2-Pad32)") (class "Default")
      (node (ref "U3") (pin "32") (pinfunction "HPDIN/RSVD2_32") (pintype "bidirectional+no_connect"))
    )
  )
)
